# SPAM_LPF_schematic.net
KiCad netlist of a schematic drawn in Altium Designer
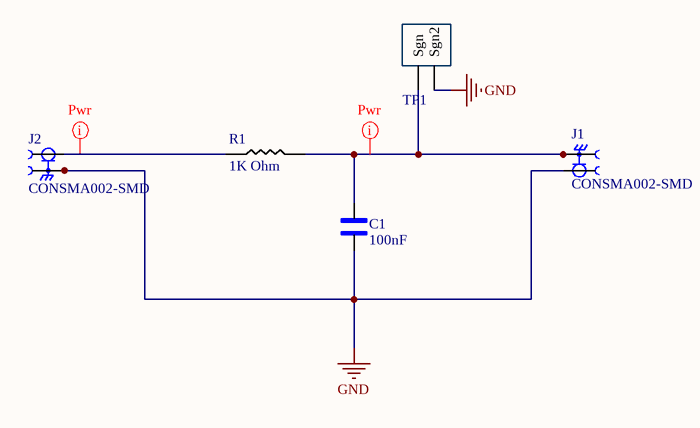
[diagram p0: SPAM_LPF_schematic.SchDoc]

(export (version "E")
  (design (tool "Eeschema 10.0.6"))
  (components
    (comp (ref "C1")
      (value "100nF")
      (footprint "1206_Passive_Capacitor")
      (description "100nF ±5% 50V C0G 1206 Multilayer Ceramic Capacitors MLCC - SMD/SMT RoHS")
      (fields (field (name "LCSC PART#") "C21812") (field (name "MFR PART #") "GRM31M5C1H473JA01L"))
      (libsource (lib "Capstone_Stock_Library") (part "C_100nF_1206"))
    )
    (comp (ref "J1")
      (value "CONSMA002-SMD")
      (footprint "TE_CONSMA002-SMD")
      (libsource (lib "CONSMA002-SMD") (part "CONSMA002-SMD"))
    )
    (comp (ref "J2")
      (value "CONSMA002-SMD")
      (footprint "TE_CONSMA002-SMD")
      (libsource (lib "CONSMA002-SMD") (part "CONSMA002-SMD"))
    )
    (comp (ref "R1")
      (value "1K Ohm")
      (footprint "1206_Passive_Resitor")
      (description "CHIP RESISTOR - SURFACE MOUNT 1KOHMS ±1% 1/4W 1206 ROHS")
      (fields (field (name "MFR PART #") "RNCP1206FTD1K00CT") (field (name "LCSC PART#") "C4410"))
      (libsource (lib "Capstone_Stock_Library") (part "R_1K_1206"))
    )
    (comp (ref "TP1")
      (value "10x Probe TP")
      (footprint "TP_Diff_Probe")
      (description "Test Point 300 mil centers")
      (libsource (lib "Capstone_Stock_Library") (part "TP_Diff_Probe"))
    )
  )
  (nets
    (net (code "1") (name "GND") (class "Default")
      (node (ref "C1") (pin "1") (pinfunction "1_1") (pintype "passive"))
      (node (ref "J1") (pin "1") (pinfunction "SIG_1") (pintype "passive"))
      (node (ref "J2") (pin "2") (pinfunction "SH_2") (pintype "power_in"))
      (node (ref "J2") (pin "3") (pinfunction "SH_3") (pintype "power_in"))
      (node (ref "TP1") (pin "2") (pinfunction "Sgn2_2") (pintype "passive"))
    )
    (net (code "2") (name "Net-(J2-SIG)") (class "Default")
      (node (ref "J2") (pin "1") (pinfunction "SIG_1") (pintype "passive"))
      (node (ref "R1") (pin "1") (pinfunction "1_1") (pintype "passive"))
    )
    (net (code "3") (name "Net-(TP1-Sgn)") (class "Default")
      (node (ref "C1") (pin "2") (pinfunction "2_2") (pintype "passive"))
      (node (ref "J1") (pin "2") (pinfunction "SH_2") (pintype "power_in"))
      (node (ref "J1") (pin "3") (pinfunction "SH_3") (pintype "power_in"))
      (node (ref "R1") (pin "2") (pinfunction "2_2") (pintype "passive"))
      (node (ref "TP1") (pin "1") (pinfunction "Sgn_1") (pintype "passive"))
    )
  )
)
